# HDN_Management.net
KiCad netlist of a schematic drawn in Altium Designer
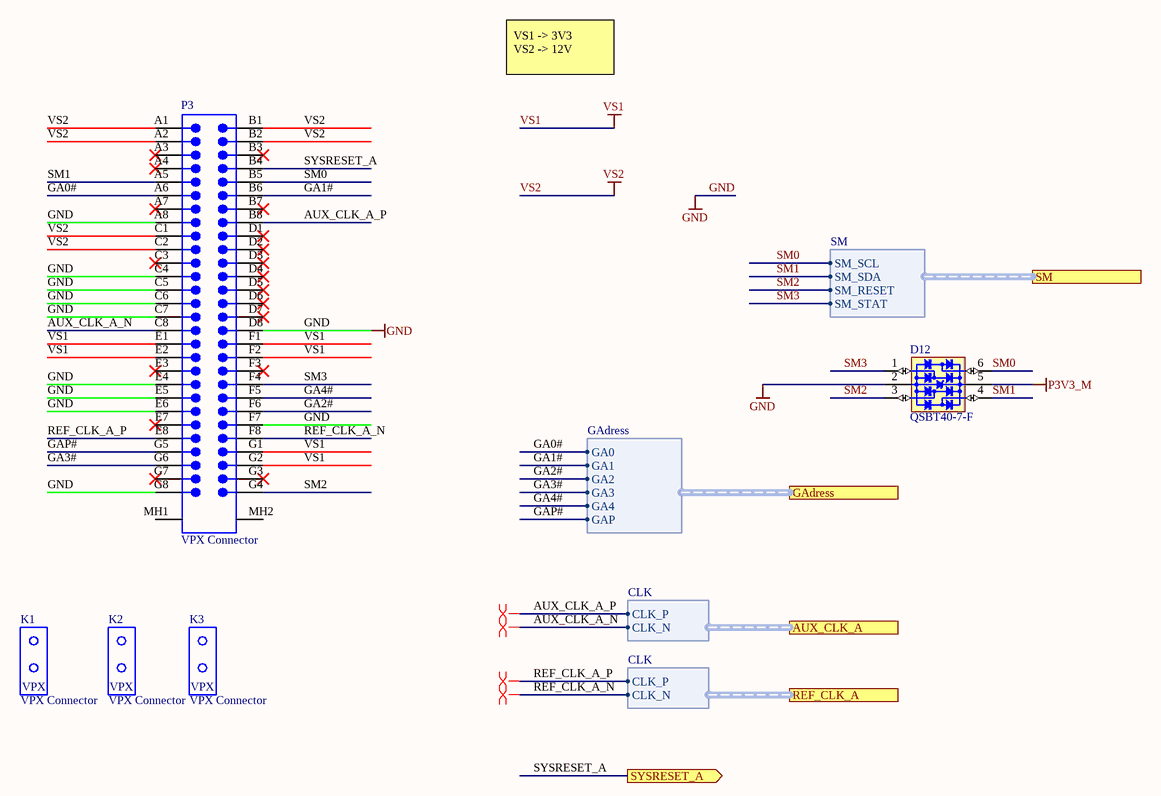
[diagram p0: HDN_Management.SchDoc]

(export (version "E")
  (design (tool "Eeschema 10.0.6"))
  (components
    (comp (ref "D12")
      (value "QSBT40-7-F")
      (footprint "SOT65P210X110-6N")
      (libsource (lib "LIBRARY_SCH") (part "D_TVS_QSBT40-7-F"))
    )
    (comp (ref "K1")
      (value "VPX Connector")
      (footprint "BTB5-5-2H2F")
      (description "VPX VITA 46 Alignment key, Right Angle, 1Key, Key orientation 0")
      (fields (field (name "MANUFACTURER") "TE") (field (name "MANUFACTURER PART NUMBER") "1469492-1"))
      (libsource (lib "LIBRARY_SCH") (part "CON_VPX_1469492-1"))
    )
    (comp (ref "K2")
      (value "VPX Connector")
      (footprint "BTB5-5-2H2F")
      (description "VPX VITA 46 Alignment key, Right Angle, 1Key, Key orientation 0")
      (fields (field (name "MANUFACTURER") "TE") (field (name "MANUFACTURER PART NUMBER") "1469492-1"))
      (libsource (lib "LIBRARY_SCH") (part "CON_VPX_1469492-1"))
    )
    (comp (ref "K3")
      (value "VPX Connector")
      (footprint "BTB5-5-2H2F")
      (description "VPX VITA 46 Alignment key, Right Angle, 1Key, Key orientation 0")
      (fields (field (name "MANUFACTURER") "TE") (field (name "MANUFACTURER PART NUMBER") "1469492-1"))
      (libsource (lib "LIBRARY_SCH") (part "CON_VPX_1469492-1"))
    )
    (comp (ref "P3")
      (value "VPX Connector")
      (footprint "BTB1-8-2H56M")
      (description "Board-to-Board Connector, Right Angle, 7-Row, Pitch 1.8mm, 56-Position")
      (fields (field (name "MANUFACTURER") "TE") (field (name "MANUFACTURER PART NUMBER") "1410189-3"))
      (libsource (lib "LIBRARY_SCH") (part "CON_VPX_1410189-3"))
    )
  )
  (nets
    (net (code "4") (name "/AUX_CLK_A_N") (class "Default")
      (node (ref "P3") (pin "C8") (pinfunction "C8_C8") (pintype "passive"))
    )
    (net (code "5") (name "/AUX_CLK_A_P") (class "Default")
      (node (ref "P3") (pin "B8") (pinfunction "B8_B8") (pintype "passive"))
    )
    (net (code "6") (name "/GA0#") (class "Default")
      (node (ref "P3") (pin "A6") (pinfunction "A6_A6") (pintype "passive"))
    )
    (net (code "7") (name "/GA1#") (class "Default")
      (node (ref "P3") (pin "B6") (pinfunction "B6_B6") (pintype "passive"))
    )
    (net (code "8") (name "/GA2#") (class "Default")
      (node (ref "P3") (pin "F6") (pinfunction "F6_F6") (pintype "passive"))
    )
    (net (code "9") (name "/GA3#") (class "Default")
      (node (ref "P3") (pin "G6") (pinfunction "G6_G6") (pintype "passive"))
    )
    (net (code "10") (name "/GA4#") (class "Default")
      (node (ref "P3") (pin "F5") (pinfunction "F5_F5") (pintype "passive"))
    )
    (net (code "11") (name "/GAP#") (class "Default")
      (node (ref "P3") (pin "G5") (pinfunction "G5_G5") (pintype "passive"))
    )
    (net (code "12") (name "/REF_CLK_A_N") (class "Default")
      (node (ref "P3") (pin "F8") (pinfunction "F8_F8") (pintype "passive"))
    )
    (net (code "13") (name "/REF_CLK_A_P") (class "Default")
      (node (ref "P3") (pin "E8") (pinfunction "E8_E8") (pintype "passive"))
    )
    (net (code "14") (name "/SM0") (class "Default")
      (node (ref "D12") (pin "6") (pinfunction "I/O4_6") (pintype "bidirectional"))
      (node (ref "P3") (pin "B5") (pinfunction "B5_B5") (pintype "passive"))
    )
    (net (code "15") (name "/SM1") (class "Default")
      (node (ref "D12") (pin "4") (pinfunction "I/O3_4") (pintype "bidirectional"))
      (node (ref "P3") (pin "A5") (pinfunction "A5_A5") (pintype "passive"))
    )
    (net (code "16") (name "/SM2") (class "Default")
      (node (ref "D12") (pin "3") (pinfunction "I/O2_3") (pintype "bidirectional"))
      (node (ref "P3") (pin "G4") (pinfunction "G4_G4") (pintype "passive"))
    )
    (net (code "17") (name "/SM3") (class "Default")
      (node (ref "D12") (pin "1") (pinfunction "I/O1_1") (pintype "bidirectional"))
      (node (ref "P3") (pin "F4") (pinfunction "F4_F4") (pintype "passive"))
    )
    (net (code "18") (name "/SYSRESET_A") (class "Default")
      (node (ref "P3") (pin "B4") (pinfunction "B4_B4") (pintype "passive"))
    )
    (net (code "22") (name "GND") (class "Default")
      (node (ref "D12") (pin "2") (pinfunction "GND_2") (pintype "power_in"))
      (node (ref "P3") (pin "A8") (pinfunction "A8_A8") (pintype "passive"))
      (node (ref "P3") (pin "C4") (pinfunction "C4_C4") (pintype "passive"))
      (node (ref "P3") (pin "C5") (pinfunction "C5_C5") (pintype "passive"))
      (node (ref "P3") (pin "C6") (pinfunction "C6_C6") (pintype "passive"))
      (node (ref "P3") (pin "C7") (pinfunction "C7_C7") (pintype "passive"))
      (node (ref "P3") (pin "D8") (pinfunction "D8_D8") (pintype "passive"))
      (node (ref "P3") (pin "E4") (pinfunction "E4_E4") (pintype "passive"))
      (node (ref "P3") (pin "E5") (pinfunction "E5_E5") (pintype "passive"))
      (node (ref "P3") (pin "E6") (pinfunction "E6_E6") (pintype "passive"))
      (node (ref "P3") (pin "F7") (pinfunction "F7_F7") (pintype "passive"))
      (node (ref "P3") (pin "G8") (pinfunction "G8_G8") (pintype "passive"))
    )
    (net (code "23") (name "P3V3_M") (class "Default")
      (node (ref "D12") (pin "5") (pinfunction "VBUS_5") (pintype "power_in"))
    )
    (net (code "24") (name "VS1") (class "Default")
      (node (ref "P3") (pin "E1") (pinfunction "E1_E1") (pintype "passive"))
      (node (ref "P3") (pin "E2") (pinfunction "E2_E2") (pintype "passive"))
      (node (ref "P3") (pin "F1") (pinfunction "F1_F1") (pintype "passive"))
      (node (ref "P3") (pin "F2") (pinfunction "F2_F2") (pintype "passive"))
      (node (ref "P3") (pin "G1") (pinfunction "G1_G1") (pintype "passive"))
      (node (ref "P3") (pin "G2") (pinfunction "G2_G2") (pintype "passive"))
    )
    (net (code "25") (name "VS2") (class "Default")
      (node (ref "P3") (pin "A1") (pinfunction "A1_A1") (pintype "passive"))
      (node (ref "P3") (pin "A2") (pinfunction "A2_A2") (pintype "passive"))
      (node (ref "P3") (pin "B1") (pinfunction "B1_B1") (pintype "passive"))
      (node (ref "P3") (pin "B2") (pinfunction "B2_B2") (pintype "passive"))
      (node (ref "P3") (pin "C1") (pinfunction "C1_C1") (pintype "passive"))
      (node (ref "P3") (pin "C2") (pinfunction "C2_C2") (pintype "passive"))
    )
    (net (code "26") (name "unconnected-(P3-PadA3)") (class "Default")
      (node (ref "P3") (pin "A3") (pinfunction "A3_A3") (pintype "passive+no_connect"))
    )
    (net (code "27") (name "unconnected-(P3-PadA4)") (class "Default")
      (node (ref "P3") (pin "A4") (pinfunction "A4_A4") (pintype "passive+no_connect"))
    )
    (net (code "28") (name "unconnected-(P3-PadA7)") (class "Default")
      (node (ref "P3") (pin "A7") (pinfunction "A7_A7") (pintype "passive+no_connect"))
    )
    (net (code "29") (name "unconnected-(P3-PadB3)") (class "Default")
      (node (ref "P3") (pin "B3") (pinfunction "B3_B3") (pintype "passive+no_connect"))
    )
    (net (code "30") (name "unconnected-(P3-PadB7)") (class "Default")
      (node (ref "P3") (pin "B7") (pinfunction "B7_B7") (pintype "passive+no_connect"))
    )
    (net (code "31") (name "unconnected-(P3-PadC3)") (class "Default")
      (node (ref "P3") (pin "C3") (pinfunction "C3_C3") (pintype "passive+no_connect"))
    )
    (net (code "32") (name "unconnected-(P3-PadD1)") (class "Default")
      (node (ref "P3") (pin "D1") (pinfunction "D1_D1") (pintype "passive+no_connect"))
    )
    (net (code "33") (name "unconnected-(P3-PadD2)") (class "Default")
      (node (ref "P3") (pin "D2") (pinfunction "D2_D2") (pintype "passive+no_connect"))
    )
    (net (code "34") (name "unconnected-(P3-PadD3)") (class "Default")
      (node (ref "P3") (pin "D3") (pinfunction "D3_D3") (pintype "passive+no_connect"))
    )
    (net (code "35") (name "unconnected-(P3-PadD4)") (class "Default")
      (node (ref "P3") (pin "D4") (pinfunction "D4_D4") (pintype "passive+no_connect"))
    )
    (net (code "36") (name "unconnected-(P3-PadD5)") (class "Default")
      (node (ref "P3") (pin "D5") (pinfunction "D5_D5") (pintype "passive+no_connect"))
    )
    (net (code "37") (name "unconnected-(P3-PadD6)") (class "Default")
      (node (ref "P3") (pin "D6") (pinfunction "D6_D6") (pintype "passive+no_connect"))
    )
    (net (code "38") (name "unconnected-(P3-PadD7)") (class "Default")
      (node (ref "P3") (pin "D7") (pinfunction "D7_D7") (pintype "passive+no_connect"))
    )
    (net (code "39") (name "unconnected-(P3-PadE3)") (class "Default")
      (node (ref "P3") (pin "E3") (pinfunction "E3_E3") (pintype "passive+no_connect"))
    )
    (net (code "40") (name "unconnected-(P3-PadE7)") (class "Default")
      (node (ref "P3") (pin "E7") (pinfunction "E7_E7") (pintype "passive+no_connect"))
    )
    (net (code "41") (name "unconnected-(P3-PadF3)") (class "Default")
      (node (ref "P3") (pin "F3") (pinfunction "F3_F3") (pintype "passive+no_connect"))
    )
    (net (code "42") (name "unconnected-(P3-PadG3)") (class "Default")
      (node (ref "P3") (pin "G3") (pinfunction "G3_G3") (pintype "passive+no_connect"))
    )
    (net (code "43") (name "unconnected-(P3-PadG7)") (class "Default")
      (node (ref "P3") (pin "G7") (pinfunction "G7_G7") (pintype "passive+no_connect"))
    )
    (net (code "44") (name "unconnected-(P3-PadMH1)") (class "Default")
      (node (ref "P3") (pin "MH1") (pinfunction "MH1_MH1") (pintype "passive"))
    )
    (net (code "45") (name "unconnected-(P3-PadMH2)") (class "Default")
      (node (ref "P3") (pin "MH2") (pinfunction "MH2_MH2") (pintype "passive"))
    )
  )
)
